# circle_color.net
KiCad netlist of a schematic drawn in EAGLE
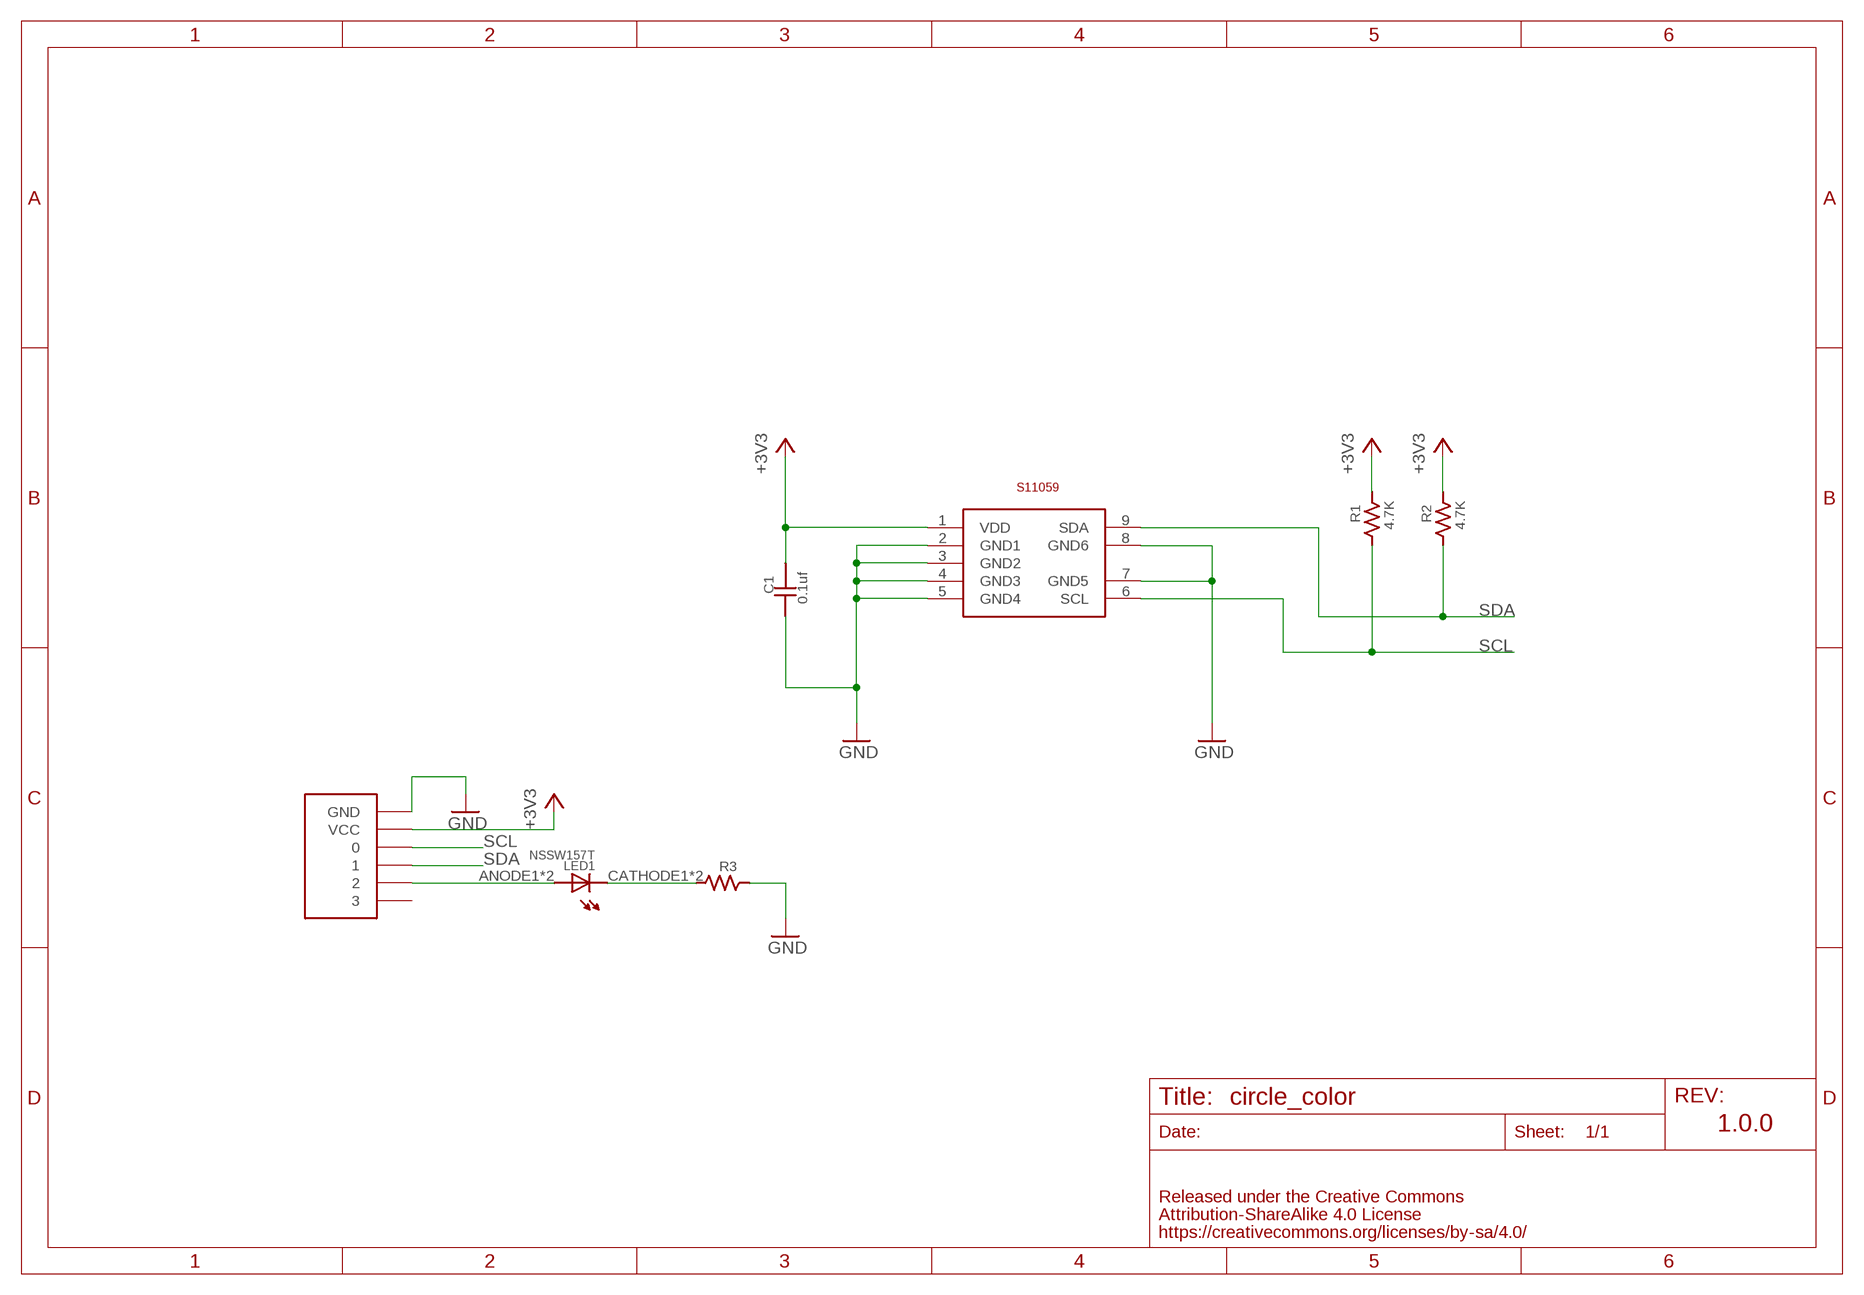
[diagram p0: schematic, sheet 1]

(export (version "E")
  (design (tool "Eeschema 10.0.6"))
  (components
    (comp (ref "C1")
      (value "0.1uf")
      (footprint "eagle-import:0402")
      (libsource (lib "eagle-import") (part "CAPACITOR0402"))
    )
    (comp (ref "LED1")
      (value "NSSW157T")
      (footprint "eagle-import:NSSW157T")
      (libsource (lib "eagle-import") (part "NSSW157T"))
    )
    (comp (ref "R1")
      (value "4.7K")
      (footprint "eagle-import:0402")
      (libsource (lib "eagle-import") (part "RESISTOR-0402"))
    )
    (comp (ref "R2")
      (value "4.7K")
      (footprint "eagle-import:0402")
      (libsource (lib "eagle-import") (part "RESISTOR-0402"))
    )
    (comp (ref "R3")
      (value "RESISTOR-0402")
      (footprint "eagle-import:0402")
      (libsource (lib "eagle-import") (part "RESISTOR-0402"))
    )
    (comp (ref "S1")
      (value "HAMAMATSU-S11059")
      (footprint "eagle-import:HAMAMATSU-S11059")
      (libsource (lib "eagle-import") (part "HAMAMATSU-S11059"))
    )
    (comp (ref "U$4")
      (value "FABO-NANO")
      (footprint "eagle-import:FABO-NANO")
      (libsource (lib "eagle-import") (part "FABO-NANO"))
    )
  )
  (nets
    (net (code "1") (name "+3V3") (class "Default")
      (node (ref "C1") (pin "P$2") (pinfunction "2_P$2") (pintype "passive"))
      (node (ref "R1") (pin "P$2") (pinfunction "2_P$2") (pintype "bidirectional"))
      (node (ref "R2") (pin "P$2") (pinfunction "2_P$2") (pintype "bidirectional"))
      (node (ref "S1") (pin "1") (pinfunction "VDD_1") (pintype "bidirectional"))
      (node (ref "U$4") (pin "VCC") (pinfunction "VCC_VCC") (pintype "bidirectional"))
    )
    (net (code "2") (name "/SCL") (class "Default")
      (node (ref "R1") (pin "P$1") (pinfunction "1_P$1") (pintype "bidirectional"))
      (node (ref "S1") (pin "6") (pinfunction "SCL_6") (pintype "bidirectional"))
      (node (ref "U$4") (pin "0") (pinfunction "0_0") (pintype "bidirectional"))
    )
    (net (code "3") (name "/SDA") (class "Default")
      (node (ref "R2") (pin "P$1") (pinfunction "1_P$1") (pintype "bidirectional"))
      (node (ref "S1") (pin "9") (pinfunction "SDA_9") (pintype "bidirectional"))
      (node (ref "U$4") (pin "1") (pinfunction "1_1") (pintype "bidirectional"))
    )
    (net (code "4") (name "GND") (class "Default")
      (node (ref "C1") (pin "P$1") (pinfunction "1_P$1") (pintype "passive"))
      (node (ref "R3") (pin "P$2") (pinfunction "2_P$2") (pintype "bidirectional"))
      (node (ref "S1") (pin "2") (pinfunction "GND1_2") (pintype "bidirectional"))
      (node (ref "S1") (pin "3") (pinfunction "GND2_3") (pintype "bidirectional"))
      (node (ref "S1") (pin "4") (pinfunction "GND3_4") (pintype "bidirectional"))
      (node (ref "S1") (pin "5") (pinfunction "GND4_5") (pintype "bidirectional"))
      (node (ref "S1") (pin "7") (pinfunction "GND5_7") (pintype "bidirectional"))
      (node (ref "S1") (pin "8") (pinfunction "GND6_8") (pintype "bidirectional"))
      (node (ref "U$4") (pin "GND") (pinfunction "GND_GND") (pintype "bidirectional"))
    )
    (net (code "5") (name "Net-(LED1-ANODE-PadANODE1)") (class "Default")
      (node (ref "LED1") (pin "ANODE1") (pinfunction "ANODE_ANODE1") (pintype "passive"))
      (node (ref "LED1") (pin "ANODE2") (pinfunction "ANODE_ANODE2") (pintype "passive"))
      (node (ref "U$4") (pin "2") (pinfunction "2_2") (pintype "bidirectional"))
    )
    (net (code "6") (name "Net-(R3-1)") (class "Default")
      (node (ref "LED1") (pin "CATHODE1") (pinfunction "CATHODE_CATHODE1") (pintype "passive"))
      (node (ref "LED1") (pin "CATHODE2") (pinfunction "CATHODE_CATHODE2") (pintype "passive"))
      (node (ref "R3") (pin "P$1") (pinfunction "1_P$1") (pintype "bidirectional"))
    )
    (net (code "7") (name "unconnected-(U$4-Pad3)") (class "Default")
      (node (ref "U$4") (pin "3") (pinfunction "3_3") (pintype "bidirectional"))
    )
  )
)
